# stm32_tb_01.net
KiCad netlist of a schematic drawn in EAGLE
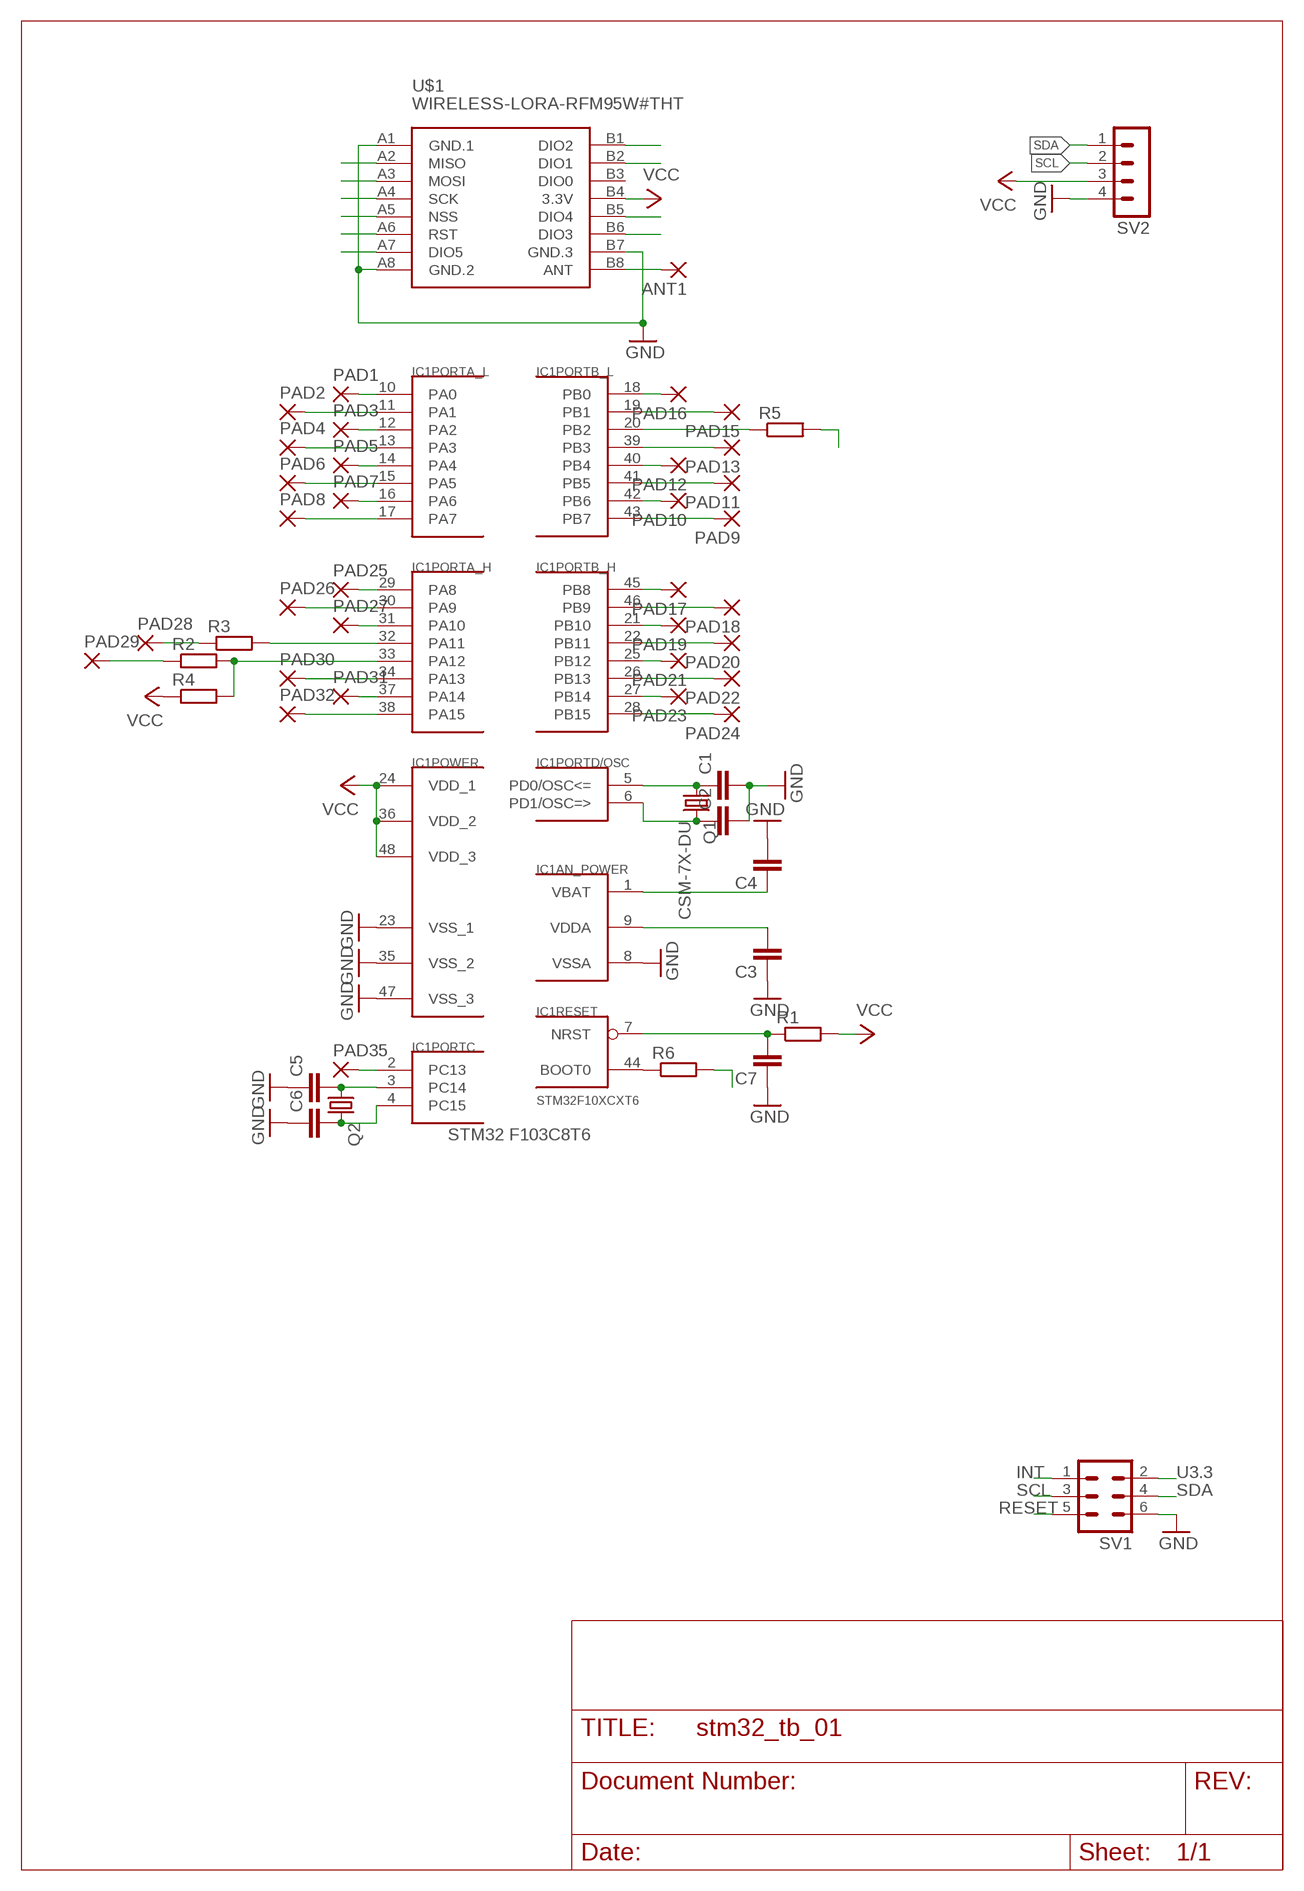
[diagram p0: schematic, sheet 1]

(export (version "E")
  (design (tool "Eeschema 10.0.6"))
  (components
    (comp (ref "ANT1")
      (value "1,6/0,9")
      (footprint "eagle-import:1,6_0,9")
      (libsource (lib "eagle-import") (part "1,6/0,9"))
    )
    (comp (ref "C1")
      (value "C-EUC0805")
      (footprint "eagle-import:C0805")
      (libsource (lib "eagle-import") (part "C-EUC0805"))
    )
    (comp (ref "C2")
      (value "C-EUC0805")
      (footprint "eagle-import:C0805")
      (libsource (lib "eagle-import") (part "C-EUC0805"))
    )
    (comp (ref "C3")
      (value "C-EUC0805")
      (footprint "eagle-import:C0805")
      (libsource (lib "eagle-import") (part "C-EUC0805"))
    )
    (comp (ref "C4")
      (value "C-EUC0805")
      (footprint "eagle-import:C0805")
      (libsource (lib "eagle-import") (part "C-EUC0805"))
    )
    (comp (ref "C5")
      (value "C-EUC0805")
      (footprint "eagle-import:C0805")
      (libsource (lib "eagle-import") (part "C-EUC0805"))
    )
    (comp (ref "C6")
      (value "C-EUC0805")
      (footprint "eagle-import:C0805")
      (libsource (lib "eagle-import") (part "C-EUC0805"))
    )
    (comp (ref "C7")
      (value "C-EUC0805")
      (footprint "eagle-import:C0805")
      (libsource (lib "eagle-import") (part "C-EUC0805"))
    )
    (comp (ref "IC1")
      (value "STM32F10XCXT6")
      (footprint "eagle-import:TQFP48")
      (libsource (lib "eagle-import") (part "STM32F10XCXT6"))
    )
    (comp (ref "PAD1")
      (value "1,6/0,9")
      (footprint "eagle-import:1,6_0,9")
      (libsource (lib "eagle-import") (part "1,6/0,9"))
    )
    (comp (ref "PAD2")
      (value "1,6/0,9")
      (footprint "eagle-import:1,6_0,9")
      (libsource (lib "eagle-import") (part "1,6/0,9"))
    )
    (comp (ref "PAD3")
      (value "1,6/0,9")
      (footprint "eagle-import:1,6_0,9")
      (libsource (lib "eagle-import") (part "1,6/0,9"))
    )
    (comp (ref "PAD4")
      (value "1,6/0,9")
      (footprint "eagle-import:1,6_0,9")
      (libsource (lib "eagle-import") (part "1,6/0,9"))
    )
    (comp (ref "PAD5")
      (value "1,6/0,9")
      (footprint "eagle-import:1,6_0,9")
      (libsource (lib "eagle-import") (part "1,6/0,9"))
    )
    (comp (ref "PAD6")
      (value "1,6/0,9")
      (footprint "eagle-import:1,6_0,9")
      (libsource (lib "eagle-import") (part "1,6/0,9"))
    )
    (comp (ref "PAD7")
      (value "1,6/0,9")
      (footprint "eagle-import:1,6_0,9")
      (libsource (lib "eagle-import") (part "1,6/0,9"))
    )
    (comp (ref "PAD8")
      (value "1,6/0,9")
      (footprint "eagle-import:1,6_0,9")
      (libsource (lib "eagle-import") (part "1,6/0,9"))
    )
    (comp (ref "PAD9")
      (value "1,6/0,9")
      (footprint "eagle-import:1,6_0,9")
      (libsource (lib "eagle-import") (part "1,6/0,9"))
    )
    (comp (ref "PAD10")
      (value "1,6/0,9")
      (footprint "eagle-import:1,6_0,9")
      (libsource (lib "eagle-import") (part "1,6/0,9"))
    )
    (comp (ref "PAD11")
      (value "1,6/0,9")
      (footprint "eagle-import:1,6_0,9")
      (libsource (lib "eagle-import") (part "1,6/0,9"))
    )
    (comp (ref "PAD12")
      (value "1,6/0,9")
      (footprint "eagle-import:1,6_0,9")
      (libsource (lib "eagle-import") (part "1,6/0,9"))
    )
    (comp (ref "PAD13")
      (value "1,6/0,9")
      (footprint "eagle-import:1,6_0,9")
      (libsource (lib "eagle-import") (part "1,6/0,9"))
    )
    (comp (ref "PAD15")
      (value "1,6/0,9")
      (footprint "eagle-import:1,6_0,9")
      (libsource (lib "eagle-import") (part "1,6/0,9"))
    )
    (comp (ref "PAD16")
      (value "1,6/0,9")
      (footprint "eagle-import:1,6_0,9")
      (libsource (lib "eagle-import") (part "1,6/0,9"))
    )
    (comp (ref "PAD17")
      (value "1,6/0,9")
      (footprint "eagle-import:1,6_0,9")
      (libsource (lib "eagle-import") (part "1,6/0,9"))
    )
    (comp (ref "PAD18")
      (value "1,6/0,9")
      (footprint "eagle-import:1,6_0,9")
      (libsource (lib "eagle-import") (part "1,6/0,9"))
    )
    (comp (ref "PAD19")
      (value "1,6/0,9")
      (footprint "eagle-import:1,6_0,9")
      (libsource (lib "eagle-import") (part "1,6/0,9"))
    )
    (comp (ref "PAD20")
      (value "1,6/0,9")
      (footprint "eagle-import:1,6_0,9")
      (libsource (lib "eagle-import") (part "1,6/0,9"))
    )
    (comp (ref "PAD21")
      (value "1,6/0,9")
      (footprint "eagle-import:1,6_0,9")
      (libsource (lib "eagle-import") (part "1,6/0,9"))
    )
    (comp (ref "PAD22")
      (value "1,6/0,9")
      (footprint "eagle-import:1,6_0,9")
      (libsource (lib "eagle-import") (part "1,6/0,9"))
    )
    (comp (ref "PAD23")
      (value "1,6/0,9")
      (footprint "eagle-import:1,6_0,9")
      (libsource (lib "eagle-import") (part "1,6/0,9"))
    )
    (comp (ref "PAD24")
      (value "1,6/0,9")
      (footprint "eagle-import:1,6_0,9")
      (libsource (lib "eagle-import") (part "1,6/0,9"))
    )
    (comp (ref "PAD25")
      (value "1,6/0,9")
      (footprint "eagle-import:1,6_0,9")
      (libsource (lib "eagle-import") (part "1,6/0,9"))
    )
    (comp (ref "PAD26")
      (value "1,6/0,9")
      (footprint "eagle-import:1,6_0,9")
      (libsource (lib "eagle-import") (part "1,6/0,9"))
    )
    (comp (ref "PAD27")
      (value "1,6/0,9")
      (footprint "eagle-import:1,6_0,9")
      (libsource (lib "eagle-import") (part "1,6/0,9"))
    )
    (comp (ref "PAD28")
      (value "1,6/0,9")
      (footprint "eagle-import:1,6_0,9")
      (libsource (lib "eagle-import") (part "1,6/0,9"))
    )
    (comp (ref "PAD29")
      (value "1,6/0,9")
      (footprint "eagle-import:1,6_0,9")
      (libsource (lib "eagle-import") (part "1,6/0,9"))
    )
    (comp (ref "PAD30")
      (value "1,6/0,9")
      (footprint "eagle-import:1,6_0,9")
      (libsource (lib "eagle-import") (part "1,6/0,9"))
    )
    (comp (ref "PAD31")
      (value "1,6/0,9")
      (footprint "eagle-import:1,6_0,9")
      (libsource (lib "eagle-import") (part "1,6/0,9"))
    )
    (comp (ref "PAD32")
      (value "1,6/0,9")
      (footprint "eagle-import:1,6_0,9")
      (libsource (lib "eagle-import") (part "1,6/0,9"))
    )
    (comp (ref "PAD35")
      (value "1,6/0,9")
      (footprint "eagle-import:1,6_0,9")
      (libsource (lib "eagle-import") (part "1,6/0,9"))
    )
    (comp (ref "Q1")
      (value "CSM-7X-DU")
      (footprint "eagle-import:CSM-7X-DU")
      (libsource (lib "eagle-import") (part "CSM-7X-DU"))
    )
    (comp (ref "Q2")
      (value "CRYSTALTC26V")
      (footprint "eagle-import:TC26V")
      (libsource (lib "eagle-import") (part "CRYSTALTC26V"))
    )
    (comp (ref "R1")
      (value "R-EU_R0805")
      (footprint "eagle-import:R0805")
      (libsource (lib "eagle-import") (part "R-EU_R0805"))
    )
    (comp (ref "R2")
      (value "R-EU_R0805")
      (footprint "eagle-import:R0805")
      (libsource (lib "eagle-import") (part "R-EU_R0805"))
    )
    (comp (ref "R3")
      (value "R-EU_R0805")
      (footprint "eagle-import:R0805")
      (libsource (lib "eagle-import") (part "R-EU_R0805"))
    )
    (comp (ref "R4")
      (value "R-EU_R0805")
      (footprint "eagle-import:R0805")
      (libsource (lib "eagle-import") (part "R-EU_R0805"))
    )
    (comp (ref "R5")
      (value "R-EU_R0805")
      (footprint "eagle-import:R0805")
      (libsource (lib "eagle-import") (part "R-EU_R0805"))
    )
    (comp (ref "R6")
      (value "R-EU_R0805")
      (footprint "eagle-import:R0805")
      (libsource (lib "eagle-import") (part "R-EU_R0805"))
    )
    (comp (ref "SV1")
      (value "ML6")
      (footprint "eagle-import:ML6")
      (libsource (lib "eagle-import") (part "ML6"))
    )
    (comp (ref "SV2")
      (value "MA04-1")
      (footprint "eagle-import:MA04-1")
      (libsource (lib "eagle-import") (part "MA04-1"))
    )
    (comp (ref "U$1")
      (value "WIRELESS-LORA-RFM95W#THT")
      (footprint "eagle-import:WIRELESS-LORA-RFM95W#THT")
      (libsource (lib "eagle-import") (part "WIRELESS-LORA-RFM95W#THT"))
    )
  )
  (nets
    (net (code "1") (name "/INT") (class "Default")
      (node (ref "SV1") (pin "1") (pinfunction "1_1") (pintype "passive"))
    )
    (net (code "2") (name "/RESET") (class "Default")
      (node (ref "SV1") (pin "5") (pinfunction "5_5") (pintype "passive"))
    )
    (net (code "3") (name "/U3.3") (class "Default")
      (node (ref "SV1") (pin "2") (pinfunction "2_2") (pintype "passive"))
    )
    (net (code "4") (name "GND") (class "Default")
      (node (ref "C1") (pin "2") (pinfunction "2_2") (pintype "passive"))
      (node (ref "C2") (pin "2") (pinfunction "2_2") (pintype "passive"))
      (node (ref "C3") (pin "1") (pinfunction "1_1") (pintype "passive"))
      (node (ref "C4") (pin "2") (pinfunction "2_2") (pintype "passive"))
      (node (ref "C5") (pin "1") (pinfunction "1_1") (pintype "passive"))
      (node (ref "C6") (pin "1") (pinfunction "1_1") (pintype "passive"))
      (node (ref "C7") (pin "1") (pinfunction "1_1") (pintype "passive"))
      (node (ref "IC1") (pin "23") (pinfunction "VSS_1_23") (pintype "power_in"))
      (node (ref "IC1") (pin "35") (pinfunction "VSS_2_35") (pintype "power_in"))
      (node (ref "IC1") (pin "47") (pinfunction "VSS_3_47") (pintype "power_in"))
      (node (ref "IC1") (pin "8") (pinfunction "VSSA_8") (pintype "power_in"))
      (node (ref "SV1") (pin "6") (pinfunction "6_6") (pintype "passive"))
      (node (ref "SV2") (pin "4") (pinfunction "4_4") (pintype "passive"))
      (node (ref "U$1") (pin "A1") (pinfunction "GND.1_A1") (pintype "power_in"))
      (node (ref "U$1") (pin "A8") (pinfunction "GND.2_A8") (pintype "power_in"))
      (node (ref "U$1") (pin "B7") (pinfunction "GND.3_B7") (pintype "power_in"))
    )
    (net (code "5") (name "Net-(ANT1-P)") (class "Default")
      (node (ref "ANT1") (pin "1") (pinfunction "P_1") (pintype "passive"))
      (node (ref "U$1") (pin "B8") (pinfunction "ANT_B8") (pintype "passive"))
    )
    (net (code "6") (name "Net-(IC1A-VBAT)") (class "Default")
      (node (ref "C4") (pin "1") (pinfunction "1_1") (pintype "passive"))
      (node (ref "IC1") (pin "1") (pinfunction "VBAT_1") (pintype "power_in"))
    )
    (net (code "7") (name "Net-(IC1A-VDDA)") (class "Default")
      (node (ref "C3") (pin "2") (pinfunction "2_2") (pintype "passive"))
      (node (ref "IC1") (pin "9") (pinfunction "VDDA_9") (pintype "power_in"))
    )
    (net (code "8") (name "Net-(IC1B-PA8)") (class "Default")
      (node (ref "IC1") (pin "29") (pinfunction "PA8_29") (pintype "bidirectional"))
      (node (ref "PAD25") (pin "1") (pinfunction "P_1") (pintype "passive"))
    )
    (net (code "9") (name "Net-(IC1B-PA9)") (class "Default")
      (node (ref "IC1") (pin "30") (pinfunction "PA9_30") (pintype "bidirectional"))
      (node (ref "PAD26") (pin "1") (pinfunction "P_1") (pintype "passive"))
    )
    (net (code "10") (name "Net-(IC1B-PA10)") (class "Default")
      (node (ref "IC1") (pin "31") (pinfunction "PA10_31") (pintype "bidirectional"))
      (node (ref "PAD27") (pin "1") (pinfunction "P_1") (pintype "passive"))
    )
    (net (code "11") (name "Net-(IC1B-PA11)") (class "Default")
      (node (ref "IC1") (pin "32") (pinfunction "PA11_32") (pintype "bidirectional"))
      (node (ref "R3") (pin "2") (pinfunction "2_2") (pintype "passive"))
    )
    (net (code "12") (name "Net-(IC1B-PA12)") (class "Default")
      (node (ref "IC1") (pin "33") (pinfunction "PA12_33") (pintype "bidirectional"))
      (node (ref "R2") (pin "2") (pinfunction "2_2") (pintype "passive"))
      (node (ref "R4") (pin "2") (pinfunction "2_2") (pintype "passive"))
    )
    (net (code "13") (name "Net-(IC1B-PA13)") (class "Default")
      (node (ref "IC1") (pin "34") (pinfunction "PA13_34") (pintype "bidirectional"))
      (node (ref "PAD30") (pin "1") (pinfunction "P_1") (pintype "passive"))
    )
    (net (code "14") (name "Net-(IC1B-PA14)") (class "Default")
      (node (ref "IC1") (pin "37") (pinfunction "PA14_37") (pintype "bidirectional"))
      (node (ref "PAD31") (pin "1") (pinfunction "P_1") (pintype "passive"))
    )
    (net (code "15") (name "Net-(IC1B-PA15)") (class "Default")
      (node (ref "IC1") (pin "38") (pinfunction "PA15_38") (pintype "bidirectional"))
      (node (ref "PAD32") (pin "1") (pinfunction "P_1") (pintype "passive"))
    )
    (net (code "16") (name "Net-(IC1C-PA0)") (class "Default")
      (node (ref "IC1") (pin "10") (pinfunction "PA0_10") (pintype "bidirectional"))
      (node (ref "PAD1") (pin "1") (pinfunction "P_1") (pintype "passive"))
    )
    (net (code "17") (name "Net-(IC1C-PA1)") (class "Default")
      (node (ref "IC1") (pin "11") (pinfunction "PA1_11") (pintype "bidirectional"))
      (node (ref "PAD2") (pin "1") (pinfunction "P_1") (pintype "passive"))
    )
    (net (code "18") (name "Net-(IC1C-PA2)") (class "Default")
      (node (ref "IC1") (pin "12") (pinfunction "PA2_12") (pintype "bidirectional"))
      (node (ref "PAD3") (pin "1") (pinfunction "P_1") (pintype "passive"))
    )
    (net (code "19") (name "Net-(IC1C-PA3)") (class "Default")
      (node (ref "IC1") (pin "13") (pinfunction "PA3_13") (pintype "bidirectional"))
      (node (ref "PAD4") (pin "1") (pinfunction "P_1") (pintype "passive"))
    )
    (net (code "20") (name "Net-(IC1C-PA4)") (class "Default")
      (node (ref "IC1") (pin "14") (pinfunction "PA4_14") (pintype "bidirectional"))
      (node (ref "PAD5") (pin "1") (pinfunction "P_1") (pintype "passive"))
    )
    (net (code "21") (name "Net-(IC1C-PA5)") (class "Default")
      (node (ref "IC1") (pin "15") (pinfunction "PA5_15") (pintype "bidirectional"))
      (node (ref "PAD6") (pin "1") (pinfunction "P_1") (pintype "passive"))
    )
    (net (code "22") (name "Net-(IC1C-PA6)") (class "Default")
      (node (ref "IC1") (pin "16") (pinfunction "PA6_16") (pintype "bidirectional"))
      (node (ref "PAD7") (pin "1") (pinfunction "P_1") (pintype "passive"))
    )
    (net (code "23") (name "Net-(IC1C-PA7)") (class "Default")
      (node (ref "IC1") (pin "17") (pinfunction "PA7_17") (pintype "bidirectional"))
      (node (ref "PAD8") (pin "1") (pinfunction "P_1") (pintype "passive"))
    )
    (net (code "24") (name "Net-(IC1D-PB8)") (class "Default")
      (node (ref "IC1") (pin "45") (pinfunction "PB8_45") (pintype "bidirectional"))
      (node (ref "PAD17") (pin "1") (pinfunction "P_1") (pintype "passive"))
    )
    (net (code "25") (name "Net-(IC1D-PB9)") (class "Default")
      (node (ref "IC1") (pin "46") (pinfunction "PB9_46") (pintype "bidirectional"))
      (node (ref "PAD18") (pin "1") (pinfunction "P_1") (pintype "passive"))
    )
    (net (code "26") (name "Net-(IC1D-PB10)") (class "Default")
      (node (ref "IC1") (pin "21") (pinfunction "PB10_21") (pintype "bidirectional"))
      (node (ref "PAD19") (pin "1") (pinfunction "P_1") (pintype "passive"))
    )
    (net (code "27") (name "Net-(IC1D-PB11)") (class "Default")
      (node (ref "IC1") (pin "22") (pinfunction "PB11_22") (pintype "bidirectional"))
      (node (ref "PAD20") (pin "1") (pinfunction "P_1") (pintype "passive"))
    )
    (net (code "28") (name "Net-(IC1D-PB12)") (class "Default")
      (node (ref "IC1") (pin "25") (pinfunction "PB12_25") (pintype "bidirectional"))
      (node (ref "PAD21") (pin "1") (pinfunction "P_1") (pintype "passive"))
    )
    (net (code "29") (name "Net-(IC1D-PB13)") (class "Default")
      (node (ref "IC1") (pin "26") (pinfunction "PB13_26") (pintype "bidirectional"))
      (node (ref "PAD22") (pin "1") (pinfunction "P_1") (pintype "passive"))
    )
    (net (code "30") (name "Net-(IC1D-PB14)") (class "Default")
      (node (ref "IC1") (pin "27") (pinfunction "PB14_27") (pintype "bidirectional"))
      (node (ref "PAD23") (pin "1") (pinfunction "P_1") (pintype "passive"))
    )
    (net (code "31") (name "Net-(IC1D-PB15)") (class "Default")
      (node (ref "IC1") (pin "28") (pinfunction "PB15_28") (pintype "bidirectional"))
      (node (ref "PAD24") (pin "1") (pinfunction "P_1") (pintype "passive"))
    )
    (net (code "32") (name "Net-(IC1E-PB0)") (class "Default")
      (node (ref "IC1") (pin "18") (pinfunction "PB0_18") (pintype "bidirectional"))
      (node (ref "PAD16") (pin "1") (pinfunction "P_1") (pintype "passive"))
    )
    (net (code "33") (name "Net-(IC1E-PB1)") (class "Default")
      (node (ref "IC1") (pin "19") (pinfunction "PB1_19") (pintype "bidirectional"))
      (node (ref "PAD15") (pin "1") (pinfunction "P_1") (pintype "passive"))
    )
    (net (code "34") (name "Net-(IC1E-PB2)") (class "Default")
      (node (ref "IC1") (pin "20") (pinfunction "PB2_20") (pintype "bidirectional"))
      (node (ref "R5") (pin "1") (pinfunction "1_1") (pintype "passive"))
    )
    (net (code "35") (name "Net-(IC1E-PB3)") (class "Default")
      (node (ref "IC1") (pin "39") (pinfunction "PB3_39") (pintype "bidirectional"))
      (node (ref "PAD13") (pin "1") (pinfunction "P_1") (pintype "passive"))
    )
    (net (code "36") (name "Net-(IC1E-PB4)") (class "Default")
      (node (ref "IC1") (pin "40") (pinfunction "PB4_40") (pintype "bidirectional"))
      (node (ref "PAD12") (pin "1") (pinfunction "P_1") (pintype "passive"))
    )
    (net (code "37") (name "Net-(IC1E-PB5)") (class "Default")
      (node (ref "IC1") (pin "41") (pinfunction "PB5_41") (pintype "bidirectional"))
      (node (ref "PAD11") (pin "1") (pinfunction "P_1") (pintype "passive"))
    )
    (net (code "38") (name "Net-(IC1E-PB6)") (class "Default")
      (node (ref "IC1") (pin "42") (pinfunction "PB6_42") (pintype "bidirectional"))
      (node (ref "PAD10") (pin "1") (pinfunction "P_1") (pintype "passive"))
    )
    (net (code "39") (name "Net-(IC1E-PB7)") (class "Default")
      (node (ref "IC1") (pin "43") (pinfunction "PB7_43") (pintype "bidirectional"))
      (node (ref "PAD9") (pin "1") (pinfunction "P_1") (pintype "passive"))
    )
    (net (code "40") (name "Net-(IC1F-PC13)") (class "Default")
      (node (ref "IC1") (pin "2") (pinfunction "PC13_2") (pintype "bidirectional"))
      (node (ref "PAD35") (pin "1") (pinfunction "P_1") (pintype "passive"))
    )
    (net (code "41") (name "Net-(IC1F-PC14)") (class "Default")
      (node (ref "C5") (pin "2") (pinfunction "2_2") (pintype "passive"))
      (node (ref "IC1") (pin "3") (pinfunction "PC14_3") (pintype "bidirectional"))
      (node (ref "Q2") (pin "1") (pinfunction "1_1") (pintype "passive"))
    )
    (net (code "42") (name "Net-(IC1F-PC15)") (class "Default")
      (node (ref "C6") (pin "2") (pinfunction "2_2") (pintype "passive"))
      (node (ref "IC1") (pin "4") (pinfunction "PC15_4") (pintype "bidirectional"))
      (node (ref "Q2") (pin "2") (pinfunction "2_2") (pintype "passive"))
    )
    (net (code "43") (name "Net-(IC1G-PD0{slash}OSC<=)") (class "Default")
      (node (ref "C1") (pin "1") (pinfunction "1_1") (pintype "passive"))
      (node (ref "IC1") (pin "5") (pinfunction "PD0/OSC<=_5") (pintype "bidirectional"))
      (node (ref "Q1") (pin "1") (pinfunction "1_1") (pintype "passive"))
    )
    (net (code "44") (name "Net-(IC1G-PD1{slash}OSC=>)") (class "Default")
      (node (ref "C2") (pin "1") (pinfunction "1_1") (pintype "passive"))
      (node (ref "IC1") (pin "6") (pinfunction "PD1/OSC=>_6") (pintype "bidirectional"))
      (node (ref "Q1") (pin "2") (pinfunction "2_2") (pintype "passive"))
    )
    (net (code "45") (name "Net-(IC1I-BOOT0)") (class "Default")
      (node (ref "IC1") (pin "44") (pinfunction "BOOT0_44") (pintype "input"))
      (node (ref "R6") (pin "1") (pinfunction "1_1") (pintype "passive"))
    )
    (net (code "46") (name "Net-(IC1I-NRST)") (class "Default")
      (node (ref "C7") (pin "2") (pinfunction "2_2") (pintype "passive"))
      (node (ref "IC1") (pin "7") (pinfunction "NRST_7") (pintype "input"))
      (node (ref "R1") (pin "1") (pinfunction "1_1") (pintype "passive"))
    )
    (net (code "47") (name "Net-(PAD28-P)") (class "Default")
      (node (ref "PAD28") (pin "1") (pinfunction "P_1") (pintype "passive"))
      (node (ref "R3") (pin "1") (pinfunction "1_1") (pintype "passive"))
    )
    (net (code "48") (name "Net-(PAD29-P)") (class "Default")
      (node (ref "PAD29") (pin "1") (pinfunction "P_1") (pintype "passive"))
      (node (ref "R2") (pin "1") (pinfunction "1_1") (pintype "passive"))
    )
    (net (code "49") (name "SCL") (class "Default")
      (node (ref "SV1") (pin "3") (pinfunction "3_3") (pintype "passive"))
      (node (ref "SV2") (pin "2") (pinfunction "2_2") (pintype "passive"))
    )
    (net (code "50") (name "SDA") (class "Default")
      (node (ref "SV1") (pin "4") (pinfunction "4_4") (pintype "passive"))
      (node (ref "SV2") (pin "1") (pinfunction "1_1") (pintype "passive"))
    )
    (net (code "51") (name "VCC") (class "Default")
      (node (ref "IC1") (pin "24") (pinfunction "VDD_1_24") (pintype "power_in"))
      (node (ref "IC1") (pin "36") (pinfunction "VDD_2_36") (pintype "power_in"))
      (node (ref "IC1") (pin "48") (pinfunction "VDD_3_48") (pintype "power_in"))
      (node (ref "R1") (pin "2") (pinfunction "2_2") (pintype "passive"))
      (node (ref "R4") (pin "1") (pinfunction "1_1") (pintype "passive"))
      (node (ref "SV2") (pin "3") (pinfunction "3_3") (pintype "passive"))
      (node (ref "U$1") (pin "B4") (pinfunction "3.3V_B4") (pintype "power_in"))
    )
    (net (code "52") (name "unconnected-(R5-Pad2)") (class "Default")
      (node (ref "R5") (pin "2") (pinfunction "2_2") (pintype "passive"))
    )
    (net (code "53") (name "unconnected-(R6-Pad2)") (class "Default")
      (node (ref "R6") (pin "2") (pinfunction "2_2") (pintype "passive"))
    )
    (net (code "54") (name "unconnected-(U$1-DIO0-PadB3)") (class "Default")
      (node (ref "U$1") (pin "B3") (pinfunction "DIO0_B3") (pintype "bidirectional"))
    )
    (net (code "55") (name "unconnected-(U$1-DIO1-PadB2)") (class "Default")
      (node (ref "U$1") (pin "B2") (pinfunction "DIO1_B2") (pintype "bidirectional"))
    )
    (net (code "56") (name "unconnected-(U$1-DIO2-PadB1)") (class "Default")
      (node (ref "U$1") (pin "B1") (pinfunction "DIO2_B1") (pintype "bidirectional"))
    )
    (net (code "57") (name "unconnected-(U$1-DIO3-PadB6)") (class "Default")
      (node (ref "U$1") (pin "B6") (pinfunction "DIO3_B6") (pintype "bidirectional"))
    )
    (net (code "58") (name "unconnected-(U$1-DIO4-PadB5)") (class "Default")
      (node (ref "U$1") (pin "B5") (pinfunction "DIO4_B5") (pintype "bidirectional"))
    )
    (net (code "59") (name "unconnected-(U$1-DIO5-PadA7)") (class "Default")
      (node (ref "U$1") (pin "A7") (pinfunction "DIO5_A7") (pintype "bidirectional"))
    )
    (net (code "60") (name "unconnected-(U$1-MISO-PadA2)") (class "Default")
      (node (ref "U$1") (pin "A2") (pinfunction "MISO_A2") (pintype "bidirectional"))
    )
    (net (code "61") (name "unconnected-(U$1-MOSI-PadA3)") (class "Default")
      (node (ref "U$1") (pin "A3") (pinfunction "MOSI_A3") (pintype "bidirectional"))
    )
    (net (code "62") (name "unconnected-(U$1-NSS-PadA5)") (class "Default")
      (node (ref "U$1") (pin "A5") (pinfunction "NSS_A5") (pintype "bidirectional"))
    )
    (net (code "63") (name "unconnected-(U$1-RST-PadA6)") (class "Default")
      (node (ref "U$1") (pin "A6") (pinfunction "RST_A6") (pintype "bidirectional"))
    )
    (net (code "64") (name "unconnected-(U$1-SCK-PadA4)") (class "Default")
      (node (ref "U$1") (pin "A4") (pinfunction "SCK_A4") (pintype "bidirectional"))
    )
  )
)
